# RPI_FEZ_DAC_00.net
KiCad netlist of a schematic drawn in Altium Designer
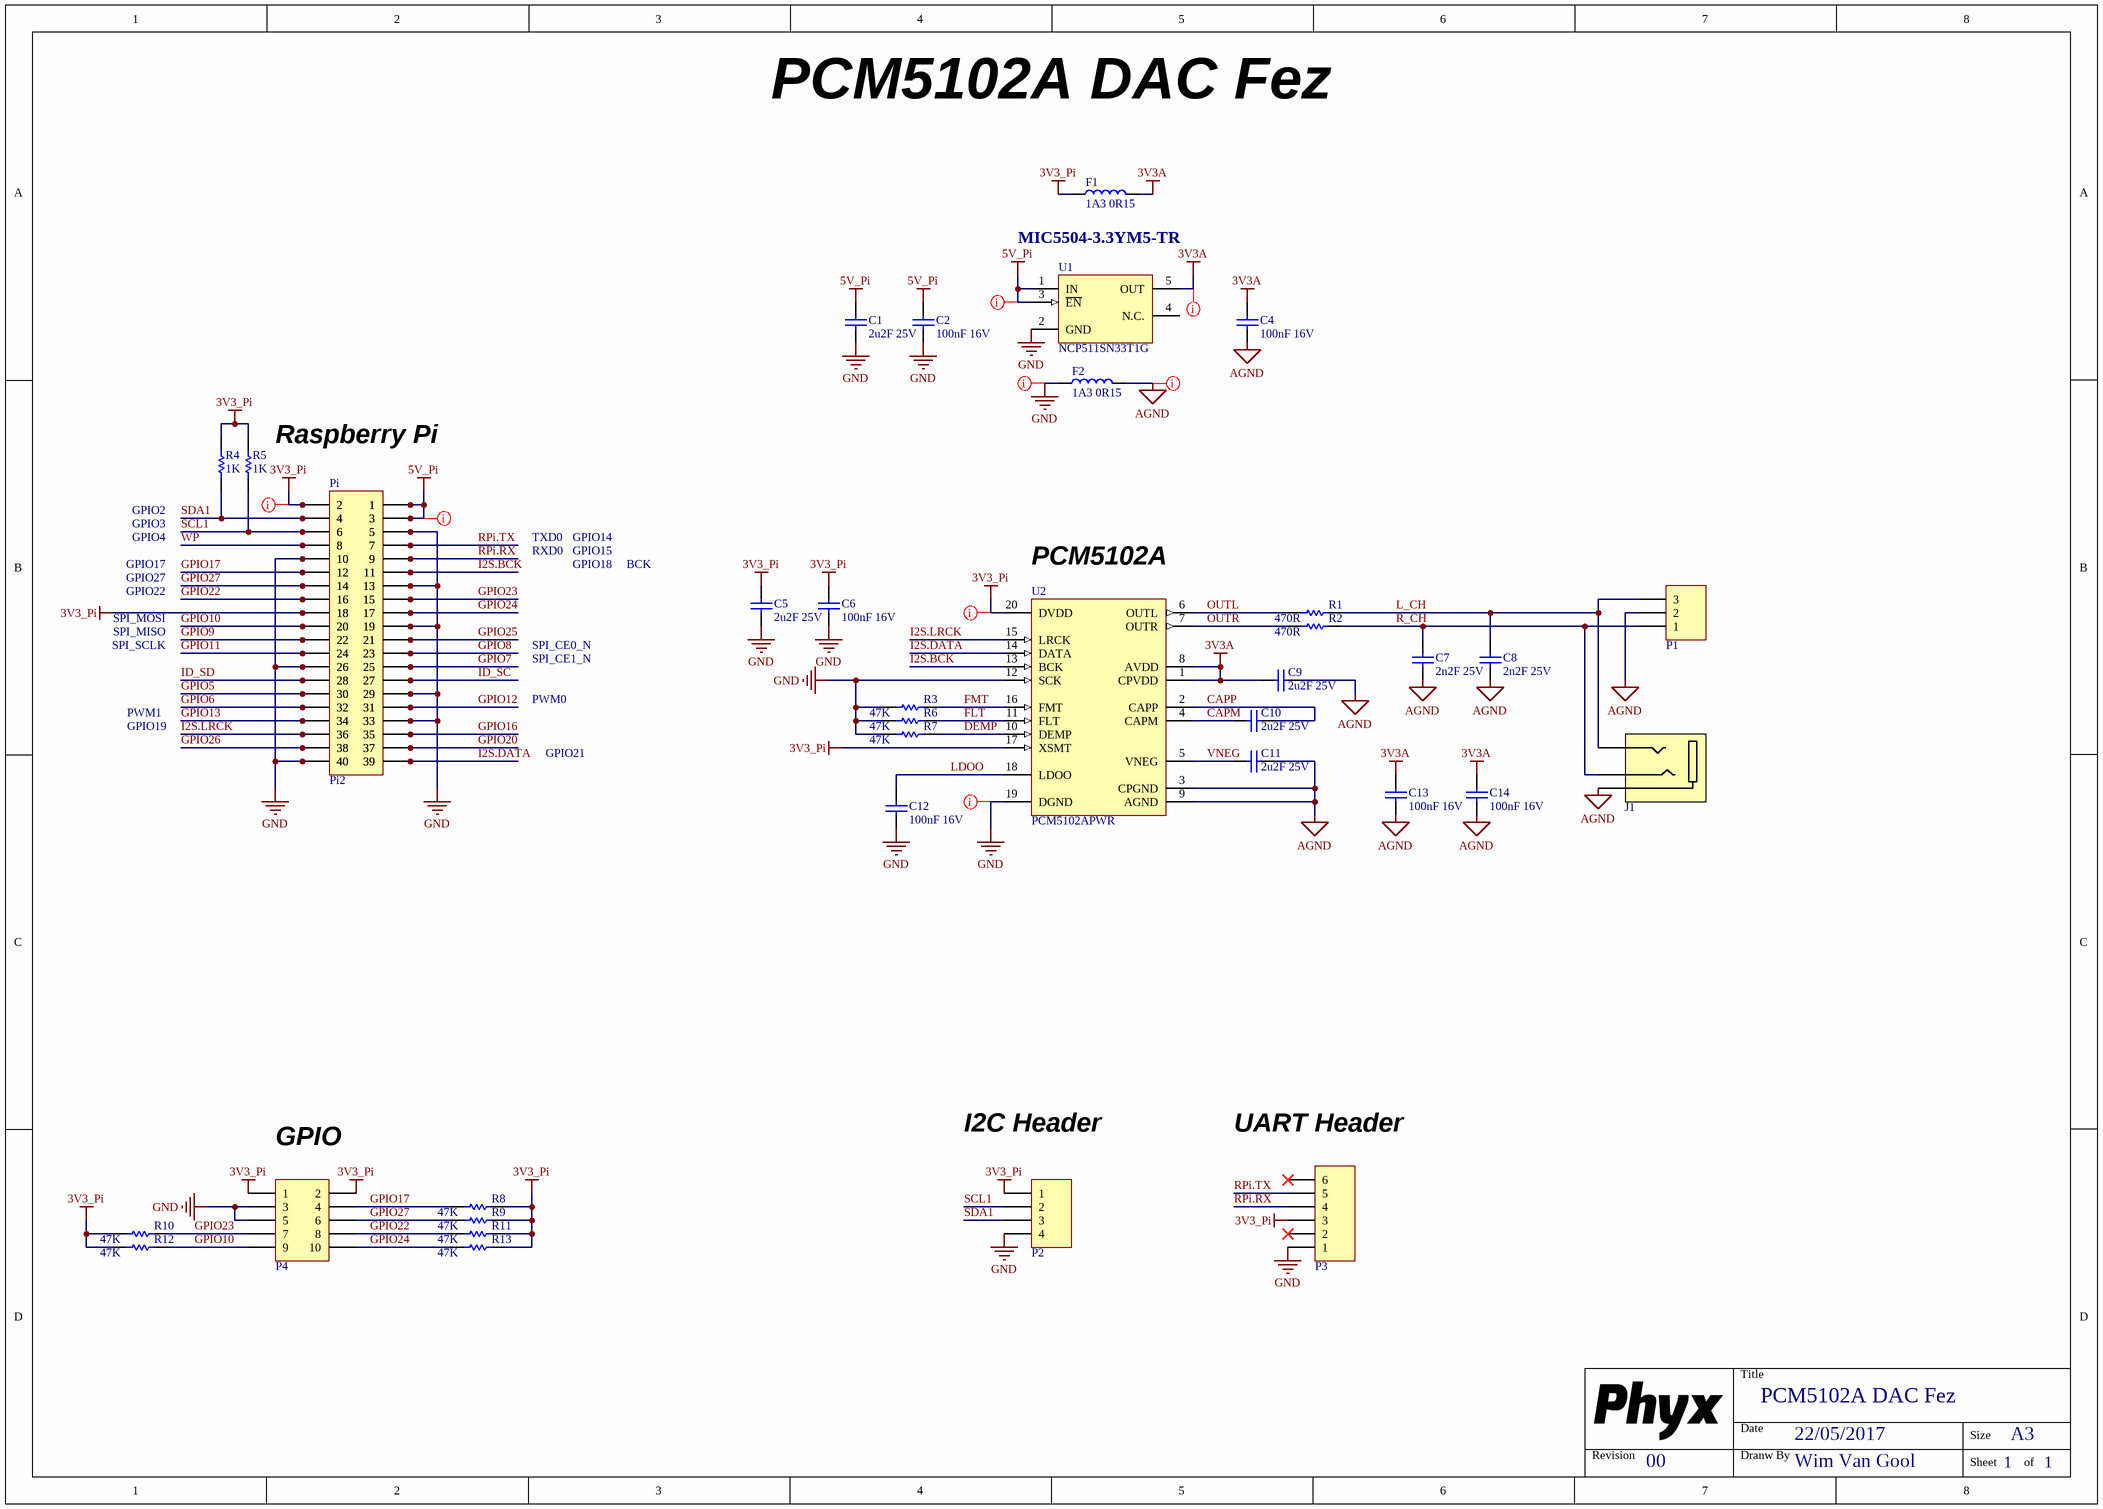
[diagram p0: RPI_FEZ_DAC_00.SchDoc]

(export (version "E")
  (design (tool "Eeschema 10.0.6"))
  (components
    (comp (ref "C1")
      (value "2u2F 25V")
      (footprint "C1206_N")
      (description "Capacitor Ceramic")
      (fields (field (name "Comment") "CAP_CERAMIC"))
      (libsource (lib "Phyx_Components") (part "CAP_CERAMIC"))
    )
    (comp (ref "C2")
      (value "100nF 16V")
      (footprint "C0603_N")
      (description "Capacitor Ceramic")
      (fields (field (name "Comment") "CAP_CERAMIC"))
      (libsource (lib "Phyx_Components") (part "CAP_CERAMIC"))
    )
    (comp (ref "C4")
      (value "100nF 16V")
      (footprint "C0603_N")
      (description "Capacitor Ceramic")
      (fields (field (name "Comment") "CAP_CERAMIC"))
      (libsource (lib "Phyx_Components") (part "CAP_CERAMIC"))
    )
    (comp (ref "C5")
      (value "2u2F 25V")
      (footprint "C1206_N")
      (description "Capacitor Ceramic")
      (fields (field (name "Comment") "CAP_CERAMIC"))
      (libsource (lib "Phyx_Components") (part "CAP_CERAMIC"))
    )
    (comp (ref "C6")
      (value "100nF 16V")
      (footprint "C0603_N")
      (description "Capacitor Ceramic")
      (fields (field (name "Comment") "CAP_CERAMIC"))
      (libsource (lib "Phyx_Components") (part "CAP_CERAMIC"))
    )
    (comp (ref "C7")
      (value "2n2F 25V")
      (footprint "C0603_N")
      (description "Capacitor Ceramic")
      (fields (field (name "Comment") "CAP_CERAMIC"))
      (libsource (lib "Phyx_Components") (part "CAP_CERAMIC"))
    )
    (comp (ref "C8")
      (value "2n2F 25V")
      (footprint "C0603_N")
      (description "Capacitor Ceramic")
      (fields (field (name "Comment") "CAP_CERAMIC"))
      (libsource (lib "Phyx_Components") (part "CAP_CERAMIC"))
    )
    (comp (ref "C9")
      (value "2u2F 25V")
      (footprint "C1206_N")
      (description "Capacitor Ceramic")
      (fields (field (name "Comment") "CAP_CERAMIC"))
      (libsource (lib "Phyx_Components") (part "CAP_CERAMIC"))
    )
    (comp (ref "C10")
      (value "2u2F 25V")
      (footprint "C1206_N")
      (description "Capacitor Ceramic")
      (fields (field (name "Comment") "CAP_CERAMIC"))
      (libsource (lib "Phyx_Components") (part "CAP_CERAMIC"))
    )
    (comp (ref "C11")
      (value "2u2F 25V")
      (footprint "C1206_N")
      (description "Capacitor Ceramic")
      (fields (field (name "Comment") "CAP_CERAMIC"))
      (libsource (lib "Phyx_Components") (part "CAP_CERAMIC"))
    )
    (comp (ref "C12")
      (value "100nF 16V")
      (footprint "C0603_N")
      (description "Capacitor Ceramic")
      (fields (field (name "Comment") "CAP_CERAMIC"))
      (libsource (lib "Phyx_Components") (part "CAP_CERAMIC"))
    )
    (comp (ref "C13")
      (value "100nF 16V")
      (footprint "C0603_N")
      (description "Capacitor Ceramic")
      (fields (field (name "Comment") "CAP_CERAMIC"))
      (libsource (lib "Phyx_Components") (part "CAP_CERAMIC"))
    )
    (comp (ref "C14")
      (value "100nF 16V")
      (footprint "C0603_N")
      (description "Capacitor Ceramic")
      (fields (field (name "Comment") "CAP_CERAMIC"))
      (libsource (lib "Phyx_Components") (part "CAP_CERAMIC"))
    )
    (comp (ref "F1")
      (value "1A3 0R15")
      (footprint "L0603")
      (fields (field (name "Comment") "BLM18KG601SN1D"))
      (libsource (lib "Phyx_Components") (part "FERRITE"))
    )
    (comp (ref "F2")
      (value "1A3 0R15")
      (footprint "L0603")
      (fields (field (name "Comment") "BLM18KG601SN1D"))
      (libsource (lib "Phyx_Components") (part "FERRITE"))
    )
    (comp (ref "J1")
      (value "3,5mm Stereo Audio Jack SMD")
      (footprint "PJ-313D")
      (description "=Description")
      (libsource (lib "Phyx_Components") (part "AUDIO_RST-123"))
    )
    (comp (ref "P1")
      (value "Header 3")
      (footprint "HDR1X3")
      (libsource (lib "Phyx_Components") (part "Header 3"))
    )
    (comp (ref "P2")
      (value "Header 4")
      (footprint "HDR1X4")
      (libsource (lib "Phyx_Components") (part "Header 4"))
    )
    (comp (ref "P3")
      (value "Header 6")
      (footprint "HDR1X6")
      (libsource (lib "Phyx_Components") (part "Header 6"))
    )
    (comp (ref "P4")
      (value "Boxed Header 5X2")
      (footprint "B_HDR2X5")
      (libsource (lib "Phyx_Components") (part "Header 5X2"))
    )
    (comp (ref "Pi")
      (value "Receptacle # 2x20 61004021821")
      (footprint "WE_61004021821")
      (description "=Description")
      (libsource (lib "Phyx_Components") (part "Header 20X2"))
    )
    (comp (ref "Pi2")
      (value "Receptacle 20X2")
      (footprint "HDR2X20")
      (description "=Description")
      (libsource (lib "Phyx_Components") (part "Header 20X2"))
    )
    (comp (ref "R1")
      (value "470R")
      (footprint "R0603_N")
      (fields (field (name "Comment") "RESISTOR"))
      (libsource (lib "Phyx_Components") (part "RESISTOR"))
    )
    (comp (ref "R2")
      (value "470R")
      (footprint "R0603_N")
      (fields (field (name "Comment") "RESISTOR"))
      (libsource (lib "Phyx_Components") (part "RESISTOR"))
    )
    (comp (ref "R3")
      (value "47K")
      (footprint "R0603_N")
      (fields (field (name "Comment") "RESISTOR"))
      (libsource (lib "Phyx_Components") (part "RESISTOR"))
    )
    (comp (ref "R4")
      (value "1K")
      (footprint "R0603_N")
      (fields (field (name "Comment") "RESISTOR"))
      (libsource (lib "Phyx_Components") (part "RESISTOR"))
    )
    (comp (ref "R5")
      (value "1K")
      (footprint "R0603_N")
      (fields (field (name "Comment") "RESISTOR"))
      (libsource (lib "Phyx_Components") (part "RESISTOR"))
    )
    (comp (ref "R6")
      (value "47K")
      (footprint "R0603_N")
      (fields (field (name "Comment") "RESISTOR"))
      (libsource (lib "Phyx_Components") (part "RESISTOR"))
    )
    (comp (ref "R7")
      (value "47K")
      (footprint "R0603_N")
      (fields (field (name "Comment") "RESISTOR"))
      (libsource (lib "Phyx_Components") (part "RESISTOR"))
    )
    (comp (ref "R8")
      (value "47K")
      (footprint "R0603_N")
      (fields (field (name "Comment") "RESISTOR"))
      (libsource (lib "Phyx_Components") (part "RESISTOR"))
    )
    (comp (ref "R9")
      (value "47K")
      (footprint "R0603_N")
      (fields (field (name "Comment") "RESISTOR"))
      (libsource (lib "Phyx_Components") (part "RESISTOR"))
    )
    (comp (ref "R10")
      (value "47K")
      (footprint "R0603_N")
      (fields (field (name "Comment") "RESISTOR"))
      (libsource (lib "Phyx_Components") (part "RESISTOR"))
    )
    (comp (ref "R11")
      (value "47K")
      (footprint "R0603_N")
      (fields (field (name "Comment") "RESISTOR"))
      (libsource (lib "Phyx_Components") (part "RESISTOR"))
    )
    (comp (ref "R12")
      (value "47K")
      (footprint "R0603_N")
      (fields (field (name "Comment") "RESISTOR"))
      (libsource (lib "Phyx_Components") (part "RESISTOR"))
    )
    (comp (ref "R13")
      (value "47K")
      (footprint "R0603_N")
      (fields (field (name "Comment") "RESISTOR"))
      (libsource (lib "Phyx_Components") (part "RESISTOR"))
    )
    (comp (ref "U1")
      (value "NCP511SN33T1G")
      (footprint "ONS_TSOP5")
      (description "=Description")
      (fields (field (name "Comment") "3V3 150mA LDO"))
      (libsource (lib "Phyx_Components") (part "NCP511SNxxT1G"))
    )
    (comp (ref "U2")
      (value "PCM5102APWR")
      (footprint "TI_PW_R-PDSO-G20")
      (description "=Description")
      (fields (field (name "Comment") "Audio Stereo DAC 32BIT 112dB"))
      (libsource (lib "Phyx_Components") (part "PCM510x"))
    )
  )
  (nets
    (net (code "1") (name "/CAPM") (class "Default")
      (node (ref "C10") (pin "2") (pinfunction "2_2") (pintype "passive"))
      (node (ref "U2") (pin "4") (pinfunction "CAPM_4") (pintype "passive"))
    )
    (net (code "2") (name "/CAPP") (class "Default")
      (node (ref "C10") (pin "1") (pinfunction "1_1") (pintype "passive"))
      (node (ref "U2") (pin "2") (pinfunction "CAPP_2") (pintype "passive"))
    )
    (net (code "3") (name "/DEMP") (class "Default")
      (node (ref "R7") (pin "1") (pinfunction "1_1") (pintype "passive"))
      (node (ref "U2") (pin "10") (pinfunction "DEMP_10") (pintype "input"))
    )
    (net (code "4") (name "/FLT") (class "Default")
      (node (ref "R6") (pin "1") (pinfunction "1_1") (pintype "passive"))
      (node (ref "U2") (pin "11") (pinfunction "FLT_11") (pintype "input"))
    )
    (net (code "5") (name "/FMT") (class "Default")
      (node (ref "R3") (pin "1") (pinfunction "1_1") (pintype "passive"))
      (node (ref "U2") (pin "16") (pinfunction "FMT_16") (pintype "input"))
    )
    (net (code "6") (name "/GPIO5") (class "Default")
      (node (ref "Pi") (pin "30") (pinfunction "30_30") (pintype "passive"))
      (node (ref "Pi2") (pin "30") (pinfunction "30_30") (pintype "passive"))
    )
    (net (code "7") (name "/GPIO6") (class "Default")
      (node (ref "Pi") (pin "32") (pinfunction "32_32") (pintype "passive"))
      (node (ref "Pi2") (pin "32") (pinfunction "32_32") (pintype "passive"))
    )
    (net (code "8") (name "/GPIO7") (class "Default")
      (node (ref "Pi") (pin "25") (pinfunction "25_25") (pintype "passive"))
      (node (ref "Pi2") (pin "25") (pinfunction "25_25") (pintype "passive"))
    )
    (net (code "9") (name "/GPIO8") (class "Default")
      (node (ref "Pi") (pin "23") (pinfunction "23_23") (pintype "passive"))
      (node (ref "Pi2") (pin "23") (pinfunction "23_23") (pintype "passive"))
    )
    (net (code "10") (name "/GPIO9") (class "Default")
      (node (ref "Pi") (pin "22") (pinfunction "22_22") (pintype "passive"))
      (node (ref "Pi2") (pin "22") (pinfunction "22_22") (pintype "passive"))
    )
    (net (code "11") (name "/GPIO10") (class "Default")
      (node (ref "P4") (pin "9") (pinfunction "9_9") (pintype "passive"))
      (node (ref "Pi") (pin "20") (pinfunction "20_20") (pintype "passive"))
      (node (ref "Pi2") (pin "20") (pinfunction "20_20") (pintype "passive"))
      (node (ref "R12") (pin "1") (pinfunction "1_1") (pintype "passive"))
    )
    (net (code "12") (name "/GPIO11") (class "Default")
      (node (ref "Pi") (pin "24") (pinfunction "24_24") (pintype "passive"))
      (node (ref "Pi2") (pin "24") (pinfunction "24_24") (pintype "passive"))
    )
    (net (code "13") (name "/GPIO12") (class "Default")
      (node (ref "Pi") (pin "31") (pinfunction "31_31") (pintype "passive"))
      (node (ref "Pi2") (pin "31") (pinfunction "31_31") (pintype "passive"))
    )
    (net (code "14") (name "/GPIO13") (class "Default")
      (node (ref "Pi") (pin "34") (pinfunction "34_34") (pintype "passive"))
      (node (ref "Pi2") (pin "34") (pinfunction "34_34") (pintype "passive"))
    )
    (net (code "15") (name "/GPIO16") (class "Default")
      (node (ref "Pi") (pin "35") (pinfunction "35_35") (pintype "passive"))
      (node (ref "Pi2") (pin "35") (pinfunction "35_35") (pintype "passive"))
    )
    (net (code "16") (name "/GPIO17") (class "Default")
      (node (ref "P4") (pin "4") (pinfunction "4_4") (pintype "passive"))
      (node (ref "Pi") (pin "12") (pinfunction "12_12") (pintype "passive"))
      (node (ref "Pi2") (pin "12") (pinfunction "12_12") (pintype "passive"))
      (node (ref "R8") (pin "2") (pinfunction "2_2") (pintype "passive"))
    )
    (net (code "17") (name "/GPIO20") (class "Default")
      (node (ref "Pi") (pin "37") (pinfunction "37_37") (pintype "passive"))
      (node (ref "Pi2") (pin "37") (pinfunction "37_37") (pintype "passive"))
    )
    (net (code "18") (name "/GPIO22") (class "Default")
      (node (ref "P4") (pin "8") (pinfunction "8_8") (pintype "passive"))
      (node (ref "Pi") (pin "16") (pinfunction "16_16") (pintype "passive"))
      (node (ref "Pi2") (pin "16") (pinfunction "16_16") (pintype "passive"))
      (node (ref "R11") (pin "2") (pinfunction "2_2") (pintype "passive"))
    )
    (net (code "19") (name "/GPIO23") (class "Default")
      (node (ref "P4") (pin "7") (pinfunction "7_7") (pintype "passive"))
      (node (ref "Pi") (pin "15") (pinfunction "15_15") (pintype "passive"))
      (node (ref "Pi2") (pin "15") (pinfunction "15_15") (pintype "passive"))
      (node (ref "R10") (pin "1") (pinfunction "1_1") (pintype "passive"))
    )
    (net (code "20") (name "/GPIO24") (class "Default")
      (node (ref "P4") (pin "10") (pinfunction "10_10") (pintype "passive"))
      (node (ref "Pi") (pin "17") (pinfunction "17_17") (pintype "passive"))
      (node (ref "Pi2") (pin "17") (pinfunction "17_17") (pintype "passive"))
      (node (ref "R13") (pin "2") (pinfunction "2_2") (pintype "passive"))
    )
    (net (code "21") (name "/GPIO25") (class "Default")
      (node (ref "Pi") (pin "21") (pinfunction "21_21") (pintype "passive"))
      (node (ref "Pi2") (pin "21") (pinfunction "21_21") (pintype "passive"))
    )
    (net (code "22") (name "/GPIO26") (class "Default")
      (node (ref "Pi") (pin "38") (pinfunction "38_38") (pintype "passive"))
      (node (ref "Pi2") (pin "38") (pinfunction "38_38") (pintype "passive"))
    )
    (net (code "23") (name "/GPIO27") (class "Default")
      (node (ref "P4") (pin "6") (pinfunction "6_6") (pintype "passive"))
      (node (ref "Pi") (pin "14") (pinfunction "14_14") (pintype "passive"))
      (node (ref "Pi2") (pin "14") (pinfunction "14_14") (pintype "passive"))
      (node (ref "R9") (pin "2") (pinfunction "2_2") (pintype "passive"))
    )
    (net (code "24") (name "/I2S.BCK") (class "Default")
      (node (ref "Pi") (pin "11") (pinfunction "11_11") (pintype "passive"))
      (node (ref "Pi2") (pin "11") (pinfunction "11_11") (pintype "passive"))
      (node (ref "U2") (pin "13") (pinfunction "BCK_13") (pintype "input"))
    )
    (net (code "25") (name "/I2S.DATA") (class "Default")
      (node (ref "Pi") (pin "39") (pinfunction "39_39") (pintype "passive"))
      (node (ref "Pi2") (pin "39") (pinfunction "39_39") (pintype "passive"))
      (node (ref "U2") (pin "14") (pinfunction "DATA_14") (pintype "input"))
    )
    (net (code "26") (name "/I2S.LRCK") (class "Default")
      (node (ref "Pi") (pin "36") (pinfunction "36_36") (pintype "passive"))
      (node (ref "Pi2") (pin "36") (pinfunction "36_36") (pintype "passive"))
      (node (ref "U2") (pin "15") (pinfunction "LRCK_15") (pintype "input"))
    )
    (net (code "27") (name "/ID_SC") (class "Default")
      (node (ref "Pi") (pin "27") (pinfunction "27_27") (pintype "passive"))
      (node (ref "Pi2") (pin "27") (pinfunction "27_27") (pintype "passive"))
    )
    (net (code "28") (name "/ID_SD") (class "Default")
      (node (ref "Pi") (pin "28") (pinfunction "28_28") (pintype "passive"))
      (node (ref "Pi2") (pin "28") (pinfunction "28_28") (pintype "passive"))
    )
    (net (code "29") (name "/LDOO") (class "Default")
      (node (ref "C12") (pin "1") (pinfunction "1_1") (pintype "passive"))
      (node (ref "U2") (pin "18") (pinfunction "LDOO_18") (pintype "power_in"))
    )
    (net (code "30") (name "/L_CH") (class "Default")
      (node (ref "C8") (pin "1") (pinfunction "1_1") (pintype "passive"))
      (node (ref "J1") (pin "2") (pinfunction "Tip_2") (pintype "passive"))
      (node (ref "P1") (pin "3") (pinfunction "3_3") (pintype "passive"))
      (node (ref "R1") (pin "1") (pinfunction "1_1") (pintype "passive"))
    )
    (net (code "31") (name "/OUTL") (class "Default")
      (node (ref "R1") (pin "2") (pinfunction "2_2") (pintype "passive"))
      (node (ref "U2") (pin "6") (pinfunction "OUTL_6") (pintype "output"))
    )
    (net (code "32") (name "/OUTR") (class "Default")
      (node (ref "R2") (pin "2") (pinfunction "2_2") (pintype "passive"))
      (node (ref "U2") (pin "7") (pinfunction "OUTR_7") (pintype "output"))
    )
    (net (code "33") (name "/RPi.RX") (class "Default")
      (node (ref "P3") (pin "4") (pinfunction "4_4") (pintype "passive"))
      (node (ref "Pi") (pin "9") (pinfunction "9_9") (pintype "passive"))
      (node (ref "Pi2") (pin "9") (pinfunction "9_9") (pintype "passive"))
    )
    (net (code "34") (name "/RPi.TX") (class "Default")
      (node (ref "P3") (pin "5") (pinfunction "5_5") (pintype "passive"))
      (node (ref "Pi") (pin "7") (pinfunction "7_7") (pintype "passive"))
      (node (ref "Pi2") (pin "7") (pinfunction "7_7") (pintype "passive"))
    )
    (net (code "35") (name "/R_CH") (class "Default")
      (node (ref "C7") (pin "1") (pinfunction "1_1") (pintype "passive"))
      (node (ref "J1") (pin "3") (pinfunction "Ring_3") (pintype "passive"))
      (node (ref "P1") (pin "1") (pinfunction "1_1") (pintype "passive"))
      (node (ref "R2") (pin "1") (pinfunction "1_1") (pintype "passive"))
    )
    (net (code "36") (name "/SCL1") (class "Default")
      (node (ref "P2") (pin "2") (pinfunction "2_2") (pintype "passive"))
      (node (ref "Pi") (pin "6") (pinfunction "6_6") (pintype "passive"))
      (node (ref "Pi2") (pin "6") (pinfunction "6_6") (pintype "passive"))
      (node (ref "R5") (pin "2") (pinfunction "2_2") (pintype "passive"))
    )
    (net (code "37") (name "/SDA1") (class "Default")
      (node (ref "P2") (pin "3") (pinfunction "3_3") (pintype "passive"))
      (node (ref "Pi") (pin "4") (pinfunction "4_4") (pintype "passive"))
      (node (ref "Pi2") (pin "4") (pinfunction "4_4") (pintype "passive"))
      (node (ref "R4") (pin "2") (pinfunction "2_2") (pintype "passive"))
    )
    (net (code "38") (name "/VNEG") (class "Default")
      (node (ref "C11") (pin "2") (pinfunction "2_2") (pintype "passive"))
      (node (ref "U2") (pin "5") (pinfunction "VNEG_5") (pintype "power_in"))
    )
    (net (code "39") (name "/WP") (class "Default")
      (node (ref "Pi") (pin "8") (pinfunction "8_8") (pintype "passive"))
      (node (ref "Pi2") (pin "8") (pinfunction "8_8") (pintype "passive"))
    )
    (net (code "40") (name "3V3A") (class "Default")
      (node (ref "C13") (pin "1") (pinfunction "1_1") (pintype "passive"))
      (node (ref "C14") (pin "1") (pinfunction "1_1") (pintype "passive"))
      (node (ref "C4") (pin "1") (pinfunction "1_1") (pintype "passive"))
      (node (ref "C9") (pin "2") (pinfunction "2_2") (pintype "passive"))
      (node (ref "F1") (pin "2") (pinfunction "2_2") (pintype "passive"))
      (node (ref "U1") (pin "5") (pinfunction "OUT_5") (pintype "power_in"))
      (node (ref "U2") (pin "1") (pinfunction "CPVDD_1") (pintype "power_in"))
      (node (ref "U2") (pin "8") (pinfunction "AVDD_8") (pintype "power_in"))
    )
    (net (code "41") (name "3V3_Pi") (class "Default")
      (node (ref "C5") (pin "1") (pinfunction "1_1") (pintype "passive"))
      (node (ref "C6") (pin "1") (pinfunction "1_1") (pintype "passive"))
      (node (ref "F1") (pin "1") (pinfunction "1_1") (pintype "passive"))
      (node (ref "P2") (pin "1") (pinfunction "1_1") (pintype "passive"))
      (node (ref "P3") (pin "3") (pinfunction "3_3") (pintype "passive"))
      (node (ref "P4") (pin "1") (pinfunction "1_1") (pintype "passive"))
      (node (ref "P4") (pin "2") (pinfunction "2_2") (pintype "passive"))
      (node (ref "Pi") (pin "18") (pinfunction "18_18") (pintype "passive"))
      (node (ref "Pi") (pin "2") (pinfunction "2_2") (pintype "passive"))
      (node (ref "Pi2") (pin "18") (pinfunction "18_18") (pintype "passive"))
      (node (ref "Pi2") (pin "2") (pinfunction "2_2") (pintype "passive"))
      (node (ref "R10") (pin "2") (pinfunction "2_2") (pintype "passive"))
      (node (ref "R11") (pin "1") (pinfunction "1_1") (pintype "passive"))
      (node (ref "R12") (pin "2") (pinfunction "2_2") (pintype "passive"))
      (node (ref "R13") (pin "1") (pinfunction "1_1") (pintype "passive"))
      (node (ref "R4") (pin "1") (pinfunction "1_1") (pintype "passive"))
      (node (ref "R5") (pin "1") (pinfunction "1_1") (pintype "passive"))
      (node (ref "R8") (pin "1") (pinfunction "1_1") (pintype "passive"))
      (node (ref "R9") (pin "1") (pinfunction "1_1") (pintype "passive"))
      (node (ref "U2") (pin "17") (pinfunction "XSMT_17") (pintype "input"))
      (node (ref "U2") (pin "20") (pinfunction "DVDD_20") (pintype "power_in"))
    )
    (net (code "42") (name "5V_Pi") (class "Default")
      (node (ref "C1") (pin "1") (pinfunction "1_1") (pintype "passive"))
      (node (ref "C2") (pin "1") (pinfunction "1_1") (pintype "passive"))
      (node (ref "Pi") (pin "1") (pinfunction "1_1") (pintype "passive"))
      (node (ref "Pi") (pin "3") (pinfunction "3_3") (pintype "passive"))
      (node (ref "Pi2") (pin "1") (pinfunction "1_1") (pintype "passive"))
      (node (ref "Pi2") (pin "3") (pinfunction "3_3") (pintype "passive"))
      (node (ref "U1") (pin "1") (pinfunction "IN_1") (pintype "power_in"))
      (node (ref "U1") (pin "3") (pinfunction "~{EN}_3") (pintype "input"))
    )
    (net (code "43") (name "AGND") (class "Default")
      (node (ref "C11") (pin "1") (pinfunction "1_1") (pintype "passive"))
      (node (ref "C13") (pin "2") (pinfunction "2_2") (pintype "passive"))
      (node (ref "C14") (pin "2") (pinfunction "2_2") (pintype "passive"))
      (node (ref "C4") (pin "2") (pinfunction "2_2") (pintype "passive"))
      (node (ref "C7") (pin "2") (pinfunction "2_2") (pintype "passive"))
      (node (ref "C8") (pin "2") (pinfunction "2_2") (pintype "passive"))
      (node (ref "C9") (pin "1") (pinfunction "1_1") (pintype "passive"))
      (node (ref "F2") (pin "2") (pinfunction "2_2") (pintype "passive"))
      (node (ref "J1") (pin "1") (pinfunction "Sleeve_1") (pintype "passive"))
      (node (ref "P1") (pin "2") (pinfunction "2_2") (pintype "passive"))
      (node (ref "U2") (pin "3") (pinfunction "CPGND_3") (pintype "power_in"))
      (node (ref "U2") (pin "9") (pinfunction "AGND_9") (pintype "power_in"))
    )
    (net (code "44") (name "GND") (class "Default")
      (node (ref "C1") (pin "2") (pinfunction "2_2") (pintype "passive"))
      (node (ref "C12") (pin "2") (pinfunction "2_2") (pintype "passive"))
      (node (ref "C2") (pin "2") (pinfunction "2_2") (pintype "passive"))
      (node (ref "C5") (pin "2") (pinfunction "2_2") (pintype "passive"))
      (node (ref "C6") (pin "2") (pinfunction "2_2") (pintype "passive"))
      (node (ref "F2") (pin "1") (pinfunction "1_1") (pintype "passive"))
      (node (ref "P2") (pin "4") (pinfunction "4_4") (pintype "passive"))
      (node (ref "P3") (pin "1") (pinfunction "1_1") (pintype "passive"))
      (node (ref "P4") (pin "3") (pinfunction "3_3") (pintype "passive"))
      (node (ref "P4") (pin "5") (pinfunction "5_5") (pintype "passive"))
      (node (ref "Pi") (pin "10") (pinfunction "10_10") (pintype "passive"))
      (node (ref "Pi") (pin "13") (pinfunction "13_13") (pintype "passive"))
      (node (ref "Pi") (pin "19") (pinfunction "19_19") (pintype "passive"))
      (node (ref "Pi") (pin "26") (pinfunction "26_26") (pintype "passive"))
      (node (ref "Pi") (pin "29") (pinfunction "29_29") (pintype "passive"))
      (node (ref "Pi") (pin "33") (pinfunction "33_33") (pintype "passive"))
      (node (ref "Pi") (pin "40") (pinfunction "40_40") (pintype "passive"))
      (node (ref "Pi") (pin "5") (pinfunction "5_5") (pintype "passive"))
      (node (ref "Pi2") (pin "10") (pinfunction "10_10") (pintype "passive"))
      (node (ref "Pi2") (pin "13") (pinfunction "13_13") (pintype "passive"))
      (node (ref "Pi2") (pin "19") (pinfunction "19_19") (pintype "passive"))
      (node (ref "Pi2") (pin "26") (pinfunction "26_26") (pintype "passive"))
      (node (ref "Pi2") (pin "29") (pinfunction "29_29") (pintype "passive"))
      (node (ref "Pi2") (pin "33") (pinfunction "33_33") (pintype "passive"))
      (node (ref "Pi2") (pin "40") (pinfunction "40_40") (pintype "passive"))
      (node (ref "Pi2") (pin "5") (pinfunction "5_5") (pintype "passive"))
      (node (ref "R3") (pin "2") (pinfunction "2_2") (pintype "passive"))
      (node (ref "R6") (pin "2") (pinfunction "2_2") (pintype "passive"))
      (node (ref "R7") (pin "2") (pinfunction "2_2") (pintype "passive"))
      (node (ref "U1") (pin "2") (pinfunction "GND_2") (pintype "power_in"))
      (node (ref "U2") (pin "12") (pinfunction "SCK_12") (pintype "input"))
      (node (ref "U2") (pin "19") (pinfunction "DGND_19") (pintype "power_in"))
    )
    (net (code "45") (name "unconnected-(P3-Pad2)") (class "Default")
      (node (ref "P3") (pin "2") (pinfunction "2_2") (pintype "passive+no_connect"))
    )
    (net (code "46") (name "unconnected-(P3-Pad6)") (class "Default")
      (node (ref "P3") (pin "6") (pinfunction "6_6") (pintype "passive+no_connect"))
    )
    (net (code "47") (name "unconnected-(U1-N.C.-Pad4)") (class "Default")
      (node (ref "U1") (pin "4") (pinfunction "N.C._4") (pintype "passive"))
    )
  )
)
